# schematic.net
KiCad netlist of a schematic drawn in EasyEDA
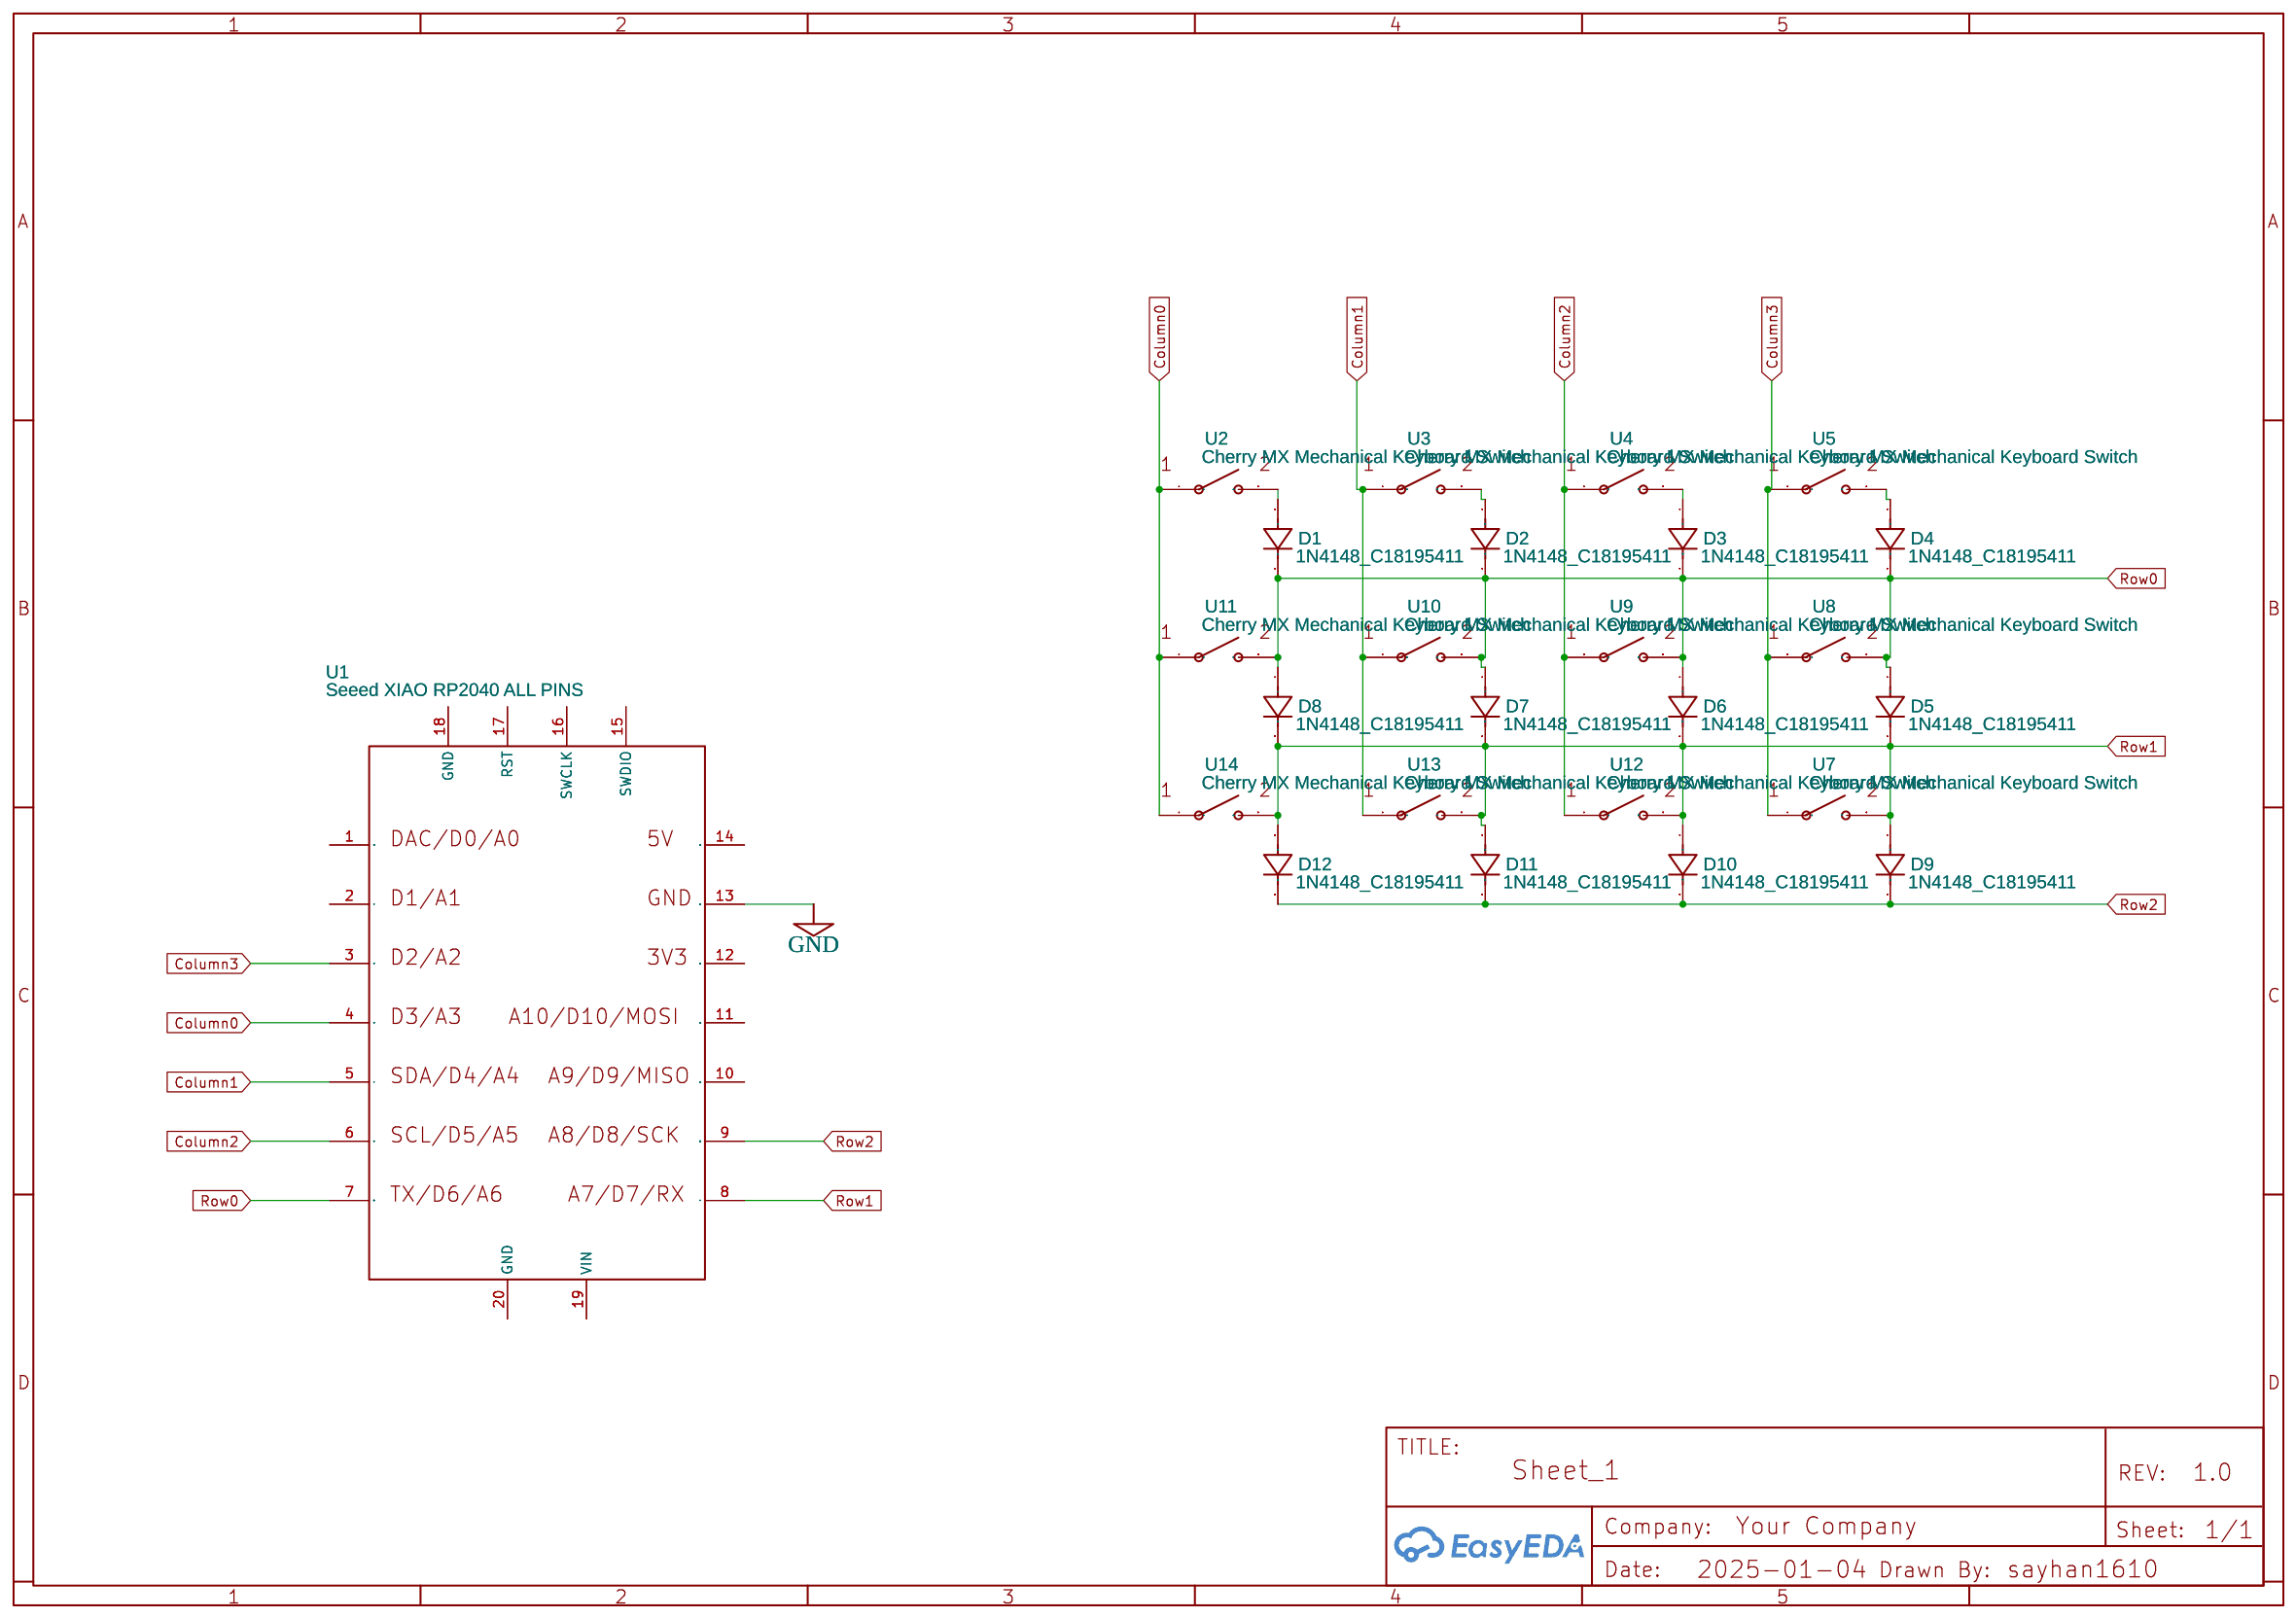
[diagram p0: schematic sheet]

(export (version "E")
  (design (tool "Eeschema 10.0.6"))
  (components
    (comp (ref "D1")
      (value "1N4148_C18195411")
      (fields (field (name "Manufacturer Part") "1N4148") (field (name "Manufacturer") "LJ(朗捷)"))
      (libsource (lib "") (part "1N4148_C18195411"))
    )
    (comp (ref "D2")
      (value "1N4148_C18195411")
      (fields (field (name "Manufacturer Part") "1N4148") (field (name "Manufacturer") "LJ(朗捷)"))
      (libsource (lib "") (part "1N4148_C18195411"))
    )
    (comp (ref "D3")
      (value "1N4148_C18195411")
      (fields (field (name "Manufacturer Part") "1N4148") (field (name "Manufacturer") "LJ(朗捷)"))
      (libsource (lib "") (part "1N4148_C18195411"))
    )
    (comp (ref "D4")
      (value "1N4148_C18195411")
      (fields (field (name "Manufacturer Part") "1N4148") (field (name "Manufacturer") "LJ(朗捷)"))
      (libsource (lib "") (part "1N4148_C18195411"))
    )
    (comp (ref "D5")
      (value "1N4148_C18195411")
      (fields (field (name "Manufacturer Part") "1N4148") (field (name "Manufacturer") "LJ(朗捷)"))
      (libsource (lib "") (part "1N4148_C18195411"))
    )
    (comp (ref "D6")
      (value "1N4148_C18195411")
      (fields (field (name "Manufacturer Part") "1N4148") (field (name "Manufacturer") "LJ(朗捷)"))
      (libsource (lib "") (part "1N4148_C18195411"))
    )
    (comp (ref "D7")
      (value "1N4148_C18195411")
      (fields (field (name "Manufacturer Part") "1N4148") (field (name "Manufacturer") "LJ(朗捷)"))
      (libsource (lib "") (part "1N4148_C18195411"))
    )
    (comp (ref "D8")
      (value "1N4148_C18195411")
      (fields (field (name "Manufacturer Part") "1N4148") (field (name "Manufacturer") "LJ(朗捷)"))
      (libsource (lib "") (part "1N4148_C18195411"))
    )
    (comp (ref "D9")
      (value "1N4148_C18195411")
      (fields (field (name "Manufacturer Part") "1N4148") (field (name "Manufacturer") "LJ(朗捷)"))
      (libsource (lib "") (part "1N4148_C18195411"))
    )
    (comp (ref "D10")
      (value "1N4148_C18195411")
      (fields (field (name "Manufacturer Part") "1N4148") (field (name "Manufacturer") "LJ(朗捷)"))
      (libsource (lib "") (part "1N4148_C18195411"))
    )
    (comp (ref "D11")
      (value "1N4148_C18195411")
      (fields (field (name "Manufacturer Part") "1N4148") (field (name "Manufacturer") "LJ(朗捷)"))
      (libsource (lib "") (part "1N4148_C18195411"))
    )
    (comp (ref "D12")
      (value "1N4148_C18195411")
      (fields (field (name "Manufacturer Part") "1N4148") (field (name "Manufacturer") "LJ(朗捷)"))
      (libsource (lib "") (part "1N4148_C18195411"))
    )
    (comp (ref "U1")
      (value "Seeed XIAO RP2040 ALL PINS")
      (fields (field (name "Manufacturer Part") "102010328") (field (name "Manufacturer") "Seeedstudio"))
      (libsource (lib "") (part "Seeed XIAO RP2040 ALL PINS"))
    )
    (comp (ref "U2")
      (value "Cherry MX Mechanical Keyboard Switch")
      (libsource (lib "") (part "Cherry MX Mechanical Keyboard Switch_1"))
    )
    (comp (ref "U3")
      (value "Cherry MX Mechanical Keyboard Switch")
      (libsource (lib "") (part "Cherry MX Mechanical Keyboard Switch"))
    )
    (comp (ref "U4")
      (value "Cherry MX Mechanical Keyboard Switch")
      (libsource (lib "") (part "Cherry MX Mechanical Keyboard Switch_1"))
    )
    (comp (ref "U5")
      (value "Cherry MX Mechanical Keyboard Switch")
      (libsource (lib "") (part "Cherry MX Mechanical Keyboard Switch"))
    )
    (comp (ref "U7")
      (value "Cherry MX Mechanical Keyboard Switch")
      (libsource (lib "") (part "Cherry MX Mechanical Keyboard Switch"))
    )
    (comp (ref "U8")
      (value "Cherry MX Mechanical Keyboard Switch")
      (libsource (lib "") (part "Cherry MX Mechanical Keyboard Switch"))
    )
    (comp (ref "U9")
      (value "Cherry MX Mechanical Keyboard Switch")
      (libsource (lib "") (part "Cherry MX Mechanical Keyboard Switch_1"))
    )
    (comp (ref "U10")
      (value "Cherry MX Mechanical Keyboard Switch")
      (libsource (lib "") (part "Cherry MX Mechanical Keyboard Switch"))
    )
    (comp (ref "U11")
      (value "Cherry MX Mechanical Keyboard Switch")
      (libsource (lib "") (part "Cherry MX Mechanical Keyboard Switch_1"))
    )
    (comp (ref "U12")
      (value "Cherry MX Mechanical Keyboard Switch")
      (libsource (lib "") (part "Cherry MX Mechanical Keyboard Switch_1"))
    )
    (comp (ref "U13")
      (value "Cherry MX Mechanical Keyboard Switch")
      (libsource (lib "") (part "Cherry MX Mechanical Keyboard Switch"))
    )
    (comp (ref "U14")
      (value "Cherry MX Mechanical Keyboard Switch")
      (libsource (lib "") (part "Cherry MX Mechanical Keyboard Switch_1"))
    )
  )
  (nets
    (net (code "1") (name "Column0") (class "Default")
      (node (ref "U1") (pin "4") (pinfunction "3_4") (pintype "unspecified"))
      (node (ref "U11") (pin "1") (pinfunction "1_1") (pintype "unspecified"))
      (node (ref "U14") (pin "1") (pinfunction "1_1") (pintype "unspecified"))
      (node (ref "U2") (pin "1") (pinfunction "1_1") (pintype "unspecified"))
    )
    (net (code "2") (name "Column1") (class "Default")
      (node (ref "U1") (pin "5") (pinfunction "4_5") (pintype "unspecified"))
      (node (ref "U10") (pin "1") (pinfunction "1_1") (pintype "unspecified"))
      (node (ref "U13") (pin "1") (pinfunction "1_1") (pintype "unspecified"))
      (node (ref "U3") (pin "1") (pinfunction "1_1") (pintype "unspecified"))
    )
    (net (code "3") (name "Column2") (class "Default")
      (node (ref "U1") (pin "6") (pinfunction "5_6") (pintype "unspecified"))
      (node (ref "U12") (pin "1") (pinfunction "1_1") (pintype "unspecified"))
      (node (ref "U4") (pin "1") (pinfunction "1_1") (pintype "unspecified"))
      (node (ref "U9") (pin "1") (pinfunction "1_1") (pintype "unspecified"))
    )
    (net (code "4") (name "Column3") (class "Default")
      (node (ref "U1") (pin "3") (pinfunction "2_3") (pintype "unspecified"))
      (node (ref "U5") (pin "1") (pinfunction "1_1") (pintype "unspecified"))
      (node (ref "U7") (pin "1") (pinfunction "1_1") (pintype "unspecified"))
      (node (ref "U8") (pin "1") (pinfunction "1_1") (pintype "unspecified"))
    )
    (net (code "5") (name "GND") (class "Default")
      (node (ref "U1") (pin "13") (pinfunction "12_13") (pintype "unspecified"))
    )
    (net (code "6") (name "Net-(D1-A)") (class "Default")
      (node (ref "D1") (pin "1") (pinfunction "A_1") (pintype "unspecified"))
      (node (ref "U2") (pin "2") (pinfunction "2_2") (pintype "unspecified"))
    )
    (net (code "7") (name "Net-(D2-A)") (class "Default")
      (node (ref "D2") (pin "1") (pinfunction "A_1") (pintype "unspecified"))
      (node (ref "U3") (pin "2") (pinfunction "2_2") (pintype "unspecified"))
    )
    (net (code "8") (name "Net-(D3-A)") (class "Default")
      (node (ref "D3") (pin "1") (pinfunction "A_1") (pintype "unspecified"))
      (node (ref "U4") (pin "2") (pinfunction "2_2") (pintype "unspecified"))
    )
    (net (code "9") (name "Net-(D4-A)") (class "Default")
      (node (ref "D4") (pin "1") (pinfunction "A_1") (pintype "unspecified"))
      (node (ref "U5") (pin "2") (pinfunction "2_2") (pintype "unspecified"))
    )
    (net (code "10") (name "Row0") (class "Default")
      (node (ref "D1") (pin "2") (pinfunction "C_2") (pintype "unspecified"))
      (node (ref "D2") (pin "2") (pinfunction "C_2") (pintype "unspecified"))
      (node (ref "D3") (pin "2") (pinfunction "C_2") (pintype "unspecified"))
      (node (ref "D4") (pin "2") (pinfunction "C_2") (pintype "unspecified"))
      (node (ref "D5") (pin "1") (pinfunction "A_1") (pintype "unspecified"))
      (node (ref "D6") (pin "1") (pinfunction "A_1") (pintype "unspecified"))
      (node (ref "D7") (pin "1") (pinfunction "A_1") (pintype "unspecified"))
      (node (ref "D8") (pin "1") (pinfunction "A_1") (pintype "unspecified"))
      (node (ref "U1") (pin "7") (pinfunction "6_7") (pintype "unspecified"))
      (node (ref "U10") (pin "2") (pinfunction "2_2") (pintype "unspecified"))
      (node (ref "U11") (pin "2") (pinfunction "2_2") (pintype "unspecified"))
      (node (ref "U8") (pin "2") (pinfunction "2_2") (pintype "unspecified"))
      (node (ref "U9") (pin "2") (pinfunction "2_2") (pintype "unspecified"))
    )
    (net (code "11") (name "Row1") (class "Default")
      (node (ref "D10") (pin "1") (pinfunction "A_1") (pintype "unspecified"))
      (node (ref "D11") (pin "1") (pinfunction "A_1") (pintype "unspecified"))
      (node (ref "D12") (pin "1") (pinfunction "A_1") (pintype "unspecified"))
      (node (ref "D5") (pin "2") (pinfunction "C_2") (pintype "unspecified"))
      (node (ref "D6") (pin "2") (pinfunction "C_2") (pintype "unspecified"))
      (node (ref "D7") (pin "2") (pinfunction "C_2") (pintype "unspecified"))
      (node (ref "D8") (pin "2") (pinfunction "C_2") (pintype "unspecified"))
      (node (ref "D9") (pin "1") (pinfunction "A_1") (pintype "unspecified"))
      (node (ref "U1") (pin "8") (pinfunction "7_8") (pintype "unspecified"))
      (node (ref "U12") (pin "2") (pinfunction "2_2") (pintype "unspecified"))
      (node (ref "U13") (pin "2") (pinfunction "2_2") (pintype "unspecified"))
      (node (ref "U14") (pin "2") (pinfunction "2_2") (pintype "unspecified"))
      (node (ref "U7") (pin "2") (pinfunction "2_2") (pintype "unspecified"))
    )
    (net (code "12") (name "Row2") (class "Default")
      (node (ref "D10") (pin "2") (pinfunction "C_2") (pintype "unspecified"))
      (node (ref "D11") (pin "2") (pinfunction "C_2") (pintype "unspecified"))
      (node (ref "D12") (pin "2") (pinfunction "C_2") (pintype "unspecified"))
      (node (ref "D9") (pin "2") (pinfunction "C_2") (pintype "unspecified"))
      (node (ref "U1") (pin "9") (pinfunction "8_9") (pintype "unspecified"))
    )
    (net (code "13") (name "unconnected-(U1-0-Pad1)") (class "Default")
      (node (ref "U1") (pin "1") (pinfunction "0_1") (pintype "unspecified"))
    )
    (net (code "14") (name "unconnected-(U1-1-Pad2)") (class "Default")
      (node (ref "U1") (pin "2") (pinfunction "1_2") (pintype "unspecified"))
    )
    (net (code "15") (name "unconnected-(U1-9-Pad10)") (class "Default")
      (node (ref "U1") (pin "10") (pinfunction "9_10") (pintype "unspecified"))
    )
    (net (code "16") (name "unconnected-(U1-10-Pad11)") (class "Default")
      (node (ref "U1") (pin "11") (pinfunction "10_11") (pintype "unspecified"))
    )
    (net (code "17") (name "unconnected-(U1-11-Pad12)") (class "Default")
      (node (ref "U1") (pin "12") (pinfunction "11_12") (pintype "unspecified"))
    )
    (net (code "18") (name "unconnected-(U1-13-Pad14)") (class "Default")
      (node (ref "U1") (pin "14") (pinfunction "13_14") (pintype "unspecified"))
    )
    (net (code "19") (name "unconnected-(U1-GND-Pad18)") (class "Default")
      (node (ref "U1") (pin "18") (pinfunction "GND_18") (pintype "unspecified"))
    )
    (net (code "20") (name "unconnected-(U1-GND-Pad20)") (class "Default")
      (node (ref "U1") (pin "20") (pinfunction "GND_20") (pintype "unspecified"))
    )
    (net (code "21") (name "unconnected-(U1-RST-Pad17)") (class "Default")
      (node (ref "U1") (pin "17") (pinfunction "RST_17") (pintype "unspecified"))
    )
    (net (code "22") (name "unconnected-(U1-SWCLK-Pad16)") (class "Default")
      (node (ref "U1") (pin "16") (pinfunction "SWCLK_16") (pintype "unspecified"))
    )
    (net (code "23") (name "unconnected-(U1-SWDIO-Pad15)") (class "Default")
      (node (ref "U1") (pin "15") (pinfunction "SWDIO_15") (pintype "unspecified"))
    )
    (net (code "24") (name "unconnected-(U1-VIN-Pad19)") (class "Default")
      (node (ref "U1") (pin "19") (pinfunction "VIN_19") (pintype "unspecified"))
    )
  )
)
